# Wizard.net
KiCad netlist of a schematic drawn in EAGLE
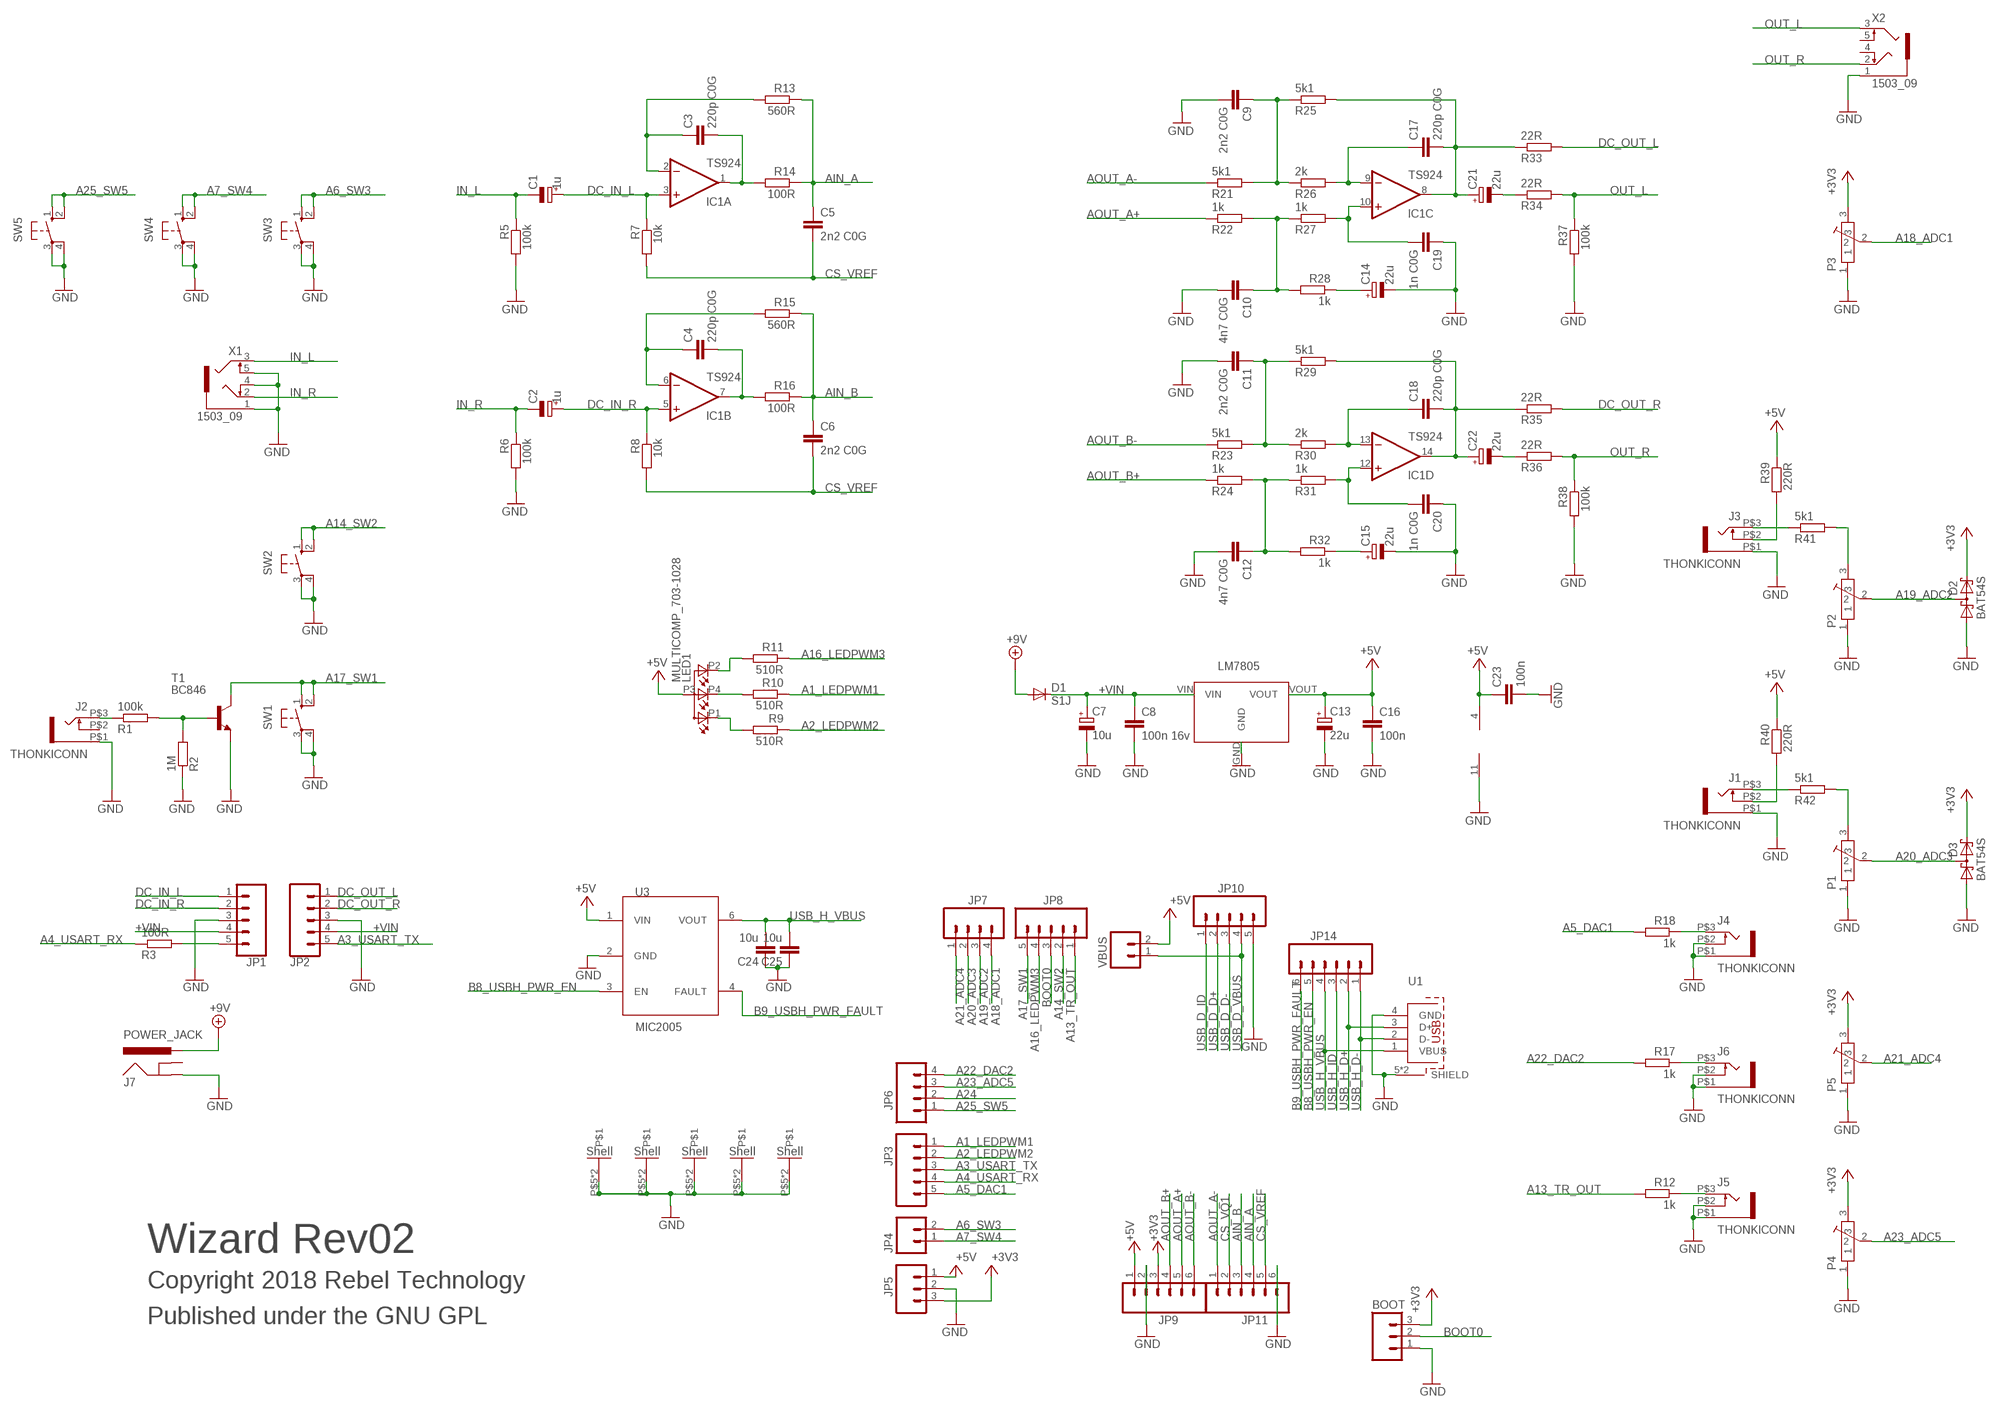
[diagram p0: schematic, sheet 1]

(export (version "E")
  (design (tool "Eeschema 10.0.6"))
  (components
    (comp (ref "BOOT")
      (value "M03PTH")
      (footprint "eagle-import:1X03")
      (libsource (lib "eagle-import") (part "M03PTH"))
    )
    (comp (ref "C1")
      (value "1u")
      (footprint "eagle-import:153CLV-0405")
      (libsource (lib "eagle-import") (part "CPOL-EU153CLV-0405"))
    )
    (comp (ref "C2")
      (value "1u")
      (footprint "eagle-import:153CLV-0405")
      (libsource (lib "eagle-import") (part "CPOL-EU153CLV-0405"))
    )
    (comp (ref "C3")
      (value "220p C0G")
      (footprint "eagle-import:C0603")
      (libsource (lib "eagle-import") (part "resistor_C-EUC0603"))
    )
    (comp (ref "C4")
      (value "220p C0G")
      (footprint "eagle-import:C0603")
      (libsource (lib "eagle-import") (part "resistor_C-EUC0603"))
    )
    (comp (ref "C5")
      (value "2n2 C0G")
      (footprint "eagle-import:C0603")
      (libsource (lib "eagle-import") (part "resistor_C-EUC0603"))
    )
    (comp (ref "C6")
      (value "2n2 C0G")
      (footprint "eagle-import:C0603")
      (libsource (lib "eagle-import") (part "resistor_C-EUC0603"))
    )
    (comp (ref "C7")
      (value "10u")
      (footprint "eagle-import:153CLV-0405")
      (libsource (lib "eagle-import") (part "CPOL-EU153CLV-0405"))
    )
    (comp (ref "C8")
      (value "100n 16v")
      (footprint "eagle-import:C0603")
      (libsource (lib "eagle-import") (part "C-EUC0603"))
    )
    (comp (ref "C9")
      (value "2n2 C0G")
      (footprint "eagle-import:C0603")
      (libsource (lib "eagle-import") (part "resistor_C-EUC0603"))
    )
    (comp (ref "C10")
      (value "4n7 C0G")
      (footprint "eagle-import:C0603")
      (libsource (lib "eagle-import") (part "resistor_C-EUC0603"))
    )
    (comp (ref "C11")
      (value "2n2 C0G")
      (footprint "eagle-import:C0603")
      (libsource (lib "eagle-import") (part "resistor_C-EUC0603"))
    )
    (comp (ref "C12")
      (value "4n7 C0G")
      (footprint "eagle-import:C0603")
      (libsource (lib "eagle-import") (part "resistor_C-EUC0603"))
    )
    (comp (ref "C13")
      (value "22u")
      (footprint "eagle-import:CPOL-5")
      (libsource (lib "eagle-import") (part "CPOL-EU153CLV-0505"))
    )
    (comp (ref "C14")
      (value "22u")
      (footprint "eagle-import:CPOL-5")
      (libsource (lib "eagle-import") (part "CPOL-EU153CLV-0505"))
    )
    (comp (ref "C15")
      (value "22u")
      (footprint "eagle-import:CPOL-5")
      (libsource (lib "eagle-import") (part "CPOL-EU153CLV-0505"))
    )
    (comp (ref "C16")
      (value "100n")
      (footprint "eagle-import:C0603")
      (libsource (lib "eagle-import") (part "C-EUC0603"))
    )
    (comp (ref "C17")
      (value "220p C0G")
      (footprint "eagle-import:C0603")
      (libsource (lib "eagle-import") (part "resistor_C-EUC0603"))
    )
    (comp (ref "C18")
      (value "220p C0G")
      (footprint "eagle-import:C0603")
      (libsource (lib "eagle-import") (part "resistor_C-EUC0603"))
    )
    (comp (ref "C19")
      (value "1n C0G")
      (footprint "eagle-import:C0603")
      (libsource (lib "eagle-import") (part "resistor_C-EUC0603"))
    )
    (comp (ref "C20")
      (value "1n C0G")
      (footprint "eagle-import:C0603")
      (libsource (lib "eagle-import") (part "resistor_C-EUC0603"))
    )
    (comp (ref "C21")
      (value "22u")
      (footprint "eagle-import:CPOL-5")
      (libsource (lib "eagle-import") (part "CPOL-EU153CLV-0505"))
    )
    (comp (ref "C22")
      (value "22u")
      (footprint "eagle-import:CPOL-5")
      (libsource (lib "eagle-import") (part "CPOL-EU153CLV-0505"))
    )
    (comp (ref "C23")
      (value "100n")
      (footprint "eagle-import:C0603")
      (libsource (lib "eagle-import") (part "resistor_C-EUC0603"))
    )
    (comp (ref "C24")
      (value "10u")
      (footprint "eagle-import:C0603")
      (libsource (lib "eagle-import") (part "resistor_C-EUC0603"))
    )
    (comp (ref "C25")
      (value "10u")
      (footprint "eagle-import:C0603")
      (libsource (lib "eagle-import") (part "resistor_C-EUC0603"))
    )
    (comp (ref "D1")
      (value "S1J")
      (footprint "eagle-import:SMA-DIODE")
      (libsource (lib "eagle-import") (part "DIODESMA"))
    )
    (comp (ref "D2")
      (value "BAT54S")
      (footprint "eagle-import:SOT23")
      (libsource (lib "eagle-import") (part "BAT54S"))
    )
    (comp (ref "D3")
      (value "BAT54S")
      (footprint "eagle-import:SOT23")
      (libsource (lib "eagle-import") (part "BAT54S"))
    )
    (comp (ref "IC1")
      (value "TS924")
      (footprint "eagle-import:SO14")
      (libsource (lib "eagle-import") (part "LM324D"))
    )
    (comp (ref "J1")
      (value "THONKICONN")
      (footprint "eagle-import:THONKICONN")
      (libsource (lib "eagle-import") (part "THONKICONN"))
    )
    (comp (ref "J2")
      (value "THONKICONN")
      (footprint "eagle-import:THONKICONN")
      (libsource (lib "eagle-import") (part "THONKICONN"))
    )
    (comp (ref "J3")
      (value "THONKICONN")
      (footprint "eagle-import:THONKICONN")
      (libsource (lib "eagle-import") (part "THONKICONN"))
    )
    (comp (ref "J4")
      (value "THONKICONN")
      (footprint "eagle-import:THONKICONN")
      (libsource (lib "eagle-import") (part "THONKICONN"))
    )
    (comp (ref "J5")
      (value "THONKICONN")
      (footprint "eagle-import:THONKICONN")
      (libsource (lib "eagle-import") (part "THONKICONN"))
    )
    (comp (ref "J6")
      (value "THONKICONN")
      (footprint "eagle-import:THONKICONN")
      (libsource (lib "eagle-import") (part "THONKICONN"))
    )
    (comp (ref "J7")
      (value "POWER_JACK")
      (footprint "eagle-import:DC_JACK_SLOT")
      (libsource (lib "eagle-import") (part "POWER_JACK"))
    )
    (comp (ref "JP1")
      (value "CONN_05JST-VERT")
      (footprint "eagle-import:JST-5-PTH-VERT")
      (libsource (lib "eagle-import") (part "CONN_05JST-VERT"))
    )
    (comp (ref "JP2")
      (value "CONN_05JST-VERT")
      (footprint "eagle-import:JST-5-PTH-VERT")
      (libsource (lib "eagle-import") (part "CONN_05JST-VERT"))
    )
    (comp (ref "JP3")
      (value "M05PTH")
      (footprint "eagle-import:1X05")
      (libsource (lib "eagle-import") (part "M05PTH"))
    )
    (comp (ref "JP4")
      (value "M02PTH")
      (footprint "eagle-import:1X02")
      (libsource (lib "eagle-import") (part "M02PTH"))
    )
    (comp (ref "JP5")
      (value "M03PTH")
      (footprint "eagle-import:1X03")
      (libsource (lib "eagle-import") (part "M03PTH"))
    )
    (comp (ref "JP6")
      (value "M04PTH")
      (footprint "eagle-import:1X04")
      (libsource (lib "eagle-import") (part "M04PTH"))
    )
    (comp (ref "JP7")
      (value "M04PTH")
      (footprint "eagle-import:1X04")
      (libsource (lib "eagle-import") (part "M04PTH"))
    )
    (comp (ref "JP8")
      (value "M05PTH")
      (footprint "eagle-import:1X05")
      (libsource (lib "eagle-import") (part "M05PTH"))
    )
    (comp (ref "JP9")
      (value "M06SIP")
      (footprint "eagle-import:1X06")
      (libsource (lib "eagle-import") (part "M06SIP"))
    )
    (comp (ref "JP10")
      (value "M05PTH")
      (footprint "eagle-import:1X05")
      (libsource (lib "eagle-import") (part "M05PTH"))
    )
    (comp (ref "JP11")
      (value "M06SIP")
      (footprint "eagle-import:1X06")
      (libsource (lib "eagle-import") (part "M06SIP"))
    )
    (comp (ref "JP14")
      (value "M06SIP")
      (footprint "eagle-import:1X06")
      (libsource (lib "eagle-import") (part "M06SIP"))
    )
    (comp (ref "LED1")
      (value "MULTICOMP_703-1028")
      (footprint "eagle-import:RGB-LED-703-1028")
      (libsource (lib "eagle-import") (part "MULTICOMP_703-1028"))
    )
    (comp (ref "P1")
      (value "POT-ALPS-RK09L1140")
      (footprint "eagle-import:POT-ALPS-RK09L1140")
      (libsource (lib "eagle-import") (part "POT-ALPS-RK09L1140"))
    )
    (comp (ref "P2")
      (value "POT-ALPS-RK09L1140")
      (footprint "eagle-import:POT-ALPS-RK09L1140")
      (libsource (lib "eagle-import") (part "POT-ALPS-RK09L1140"))
    )
    (comp (ref "P3")
      (value "POT-ALPS-RK09L1140")
      (footprint "eagle-import:POT-ALPS-RK09L1140")
      (libsource (lib "eagle-import") (part "POT-ALPS-RK09L1140"))
    )
    (comp (ref "P4")
      (value "POT-ALPS-RK09L1140")
      (footprint "eagle-import:POT-ALPS-RK09L1140")
      (libsource (lib "eagle-import") (part "POT-ALPS-RK09L1140"))
    )
    (comp (ref "P5")
      (value "POT-ALPS-RK09L1140")
      (footprint "eagle-import:POT-ALPS-RK09L1140")
      (libsource (lib "eagle-import") (part "POT-ALPS-RK09L1140"))
    )
    (comp (ref "R1")
      (value "100k")
      (footprint "eagle-import:0603")
      (libsource (lib "eagle-import") (part "R-EU_0603"))
    )
    (comp (ref "R2")
      (value "1M")
      (footprint "eagle-import:0603")
      (libsource (lib "eagle-import") (part "R-EU_0603"))
    )
    (comp (ref "R3")
      (value "100R")
      (footprint "eagle-import:0603")
      (libsource (lib "eagle-import") (part "R-EU_0603"))
    )
    (comp (ref "R5")
      (value "100k")
      (footprint "eagle-import:0603")
      (libsource (lib "eagle-import") (part "R-EU_0603"))
    )
    (comp (ref "R6")
      (value "100k")
      (footprint "eagle-import:0603")
      (libsource (lib "eagle-import") (part "R-EU_0603"))
    )
    (comp (ref "R7")
      (value "10k")
      (footprint "eagle-import:0603")
      (libsource (lib "eagle-import") (part "R-EU_0603"))
    )
    (comp (ref "R8")
      (value "10k")
      (footprint "eagle-import:0603")
      (libsource (lib "eagle-import") (part "R-EU_0603"))
    )
    (comp (ref "R9")
      (value "510R")
      (footprint "eagle-import:0603")
      (libsource (lib "eagle-import") (part "R-EU_0603"))
    )
    (comp (ref "R10")
      (value "510R")
      (footprint "eagle-import:0603")
      (libsource (lib "eagle-import") (part "R-EU_0603"))
    )
    (comp (ref "R11")
      (value "510R")
      (footprint "eagle-import:0603")
      (libsource (lib "eagle-import") (part "R-EU_0603"))
    )
    (comp (ref "R12")
      (value "1k")
      (footprint "eagle-import:0603")
      (libsource (lib "eagle-import") (part "R-EU_0603"))
    )
    (comp (ref "R13")
      (value "560R")
      (footprint "eagle-import:0603")
      (libsource (lib "eagle-import") (part "R-EU_0603"))
    )
    (comp (ref "R14")
      (value "100R")
      (footprint "eagle-import:0603")
      (libsource (lib "eagle-import") (part "R-EU_0603"))
    )
    (comp (ref "R15")
      (value "560R")
      (footprint "eagle-import:0603")
      (libsource (lib "eagle-import") (part "R-EU_0603"))
    )
    (comp (ref "R16")
      (value "100R")
      (footprint "eagle-import:0603")
      (libsource (lib "eagle-import") (part "R-EU_0603"))
    )
    (comp (ref "R17")
      (value "1k")
      (footprint "eagle-import:0603")
      (libsource (lib "eagle-import") (part "R-EU_0603"))
    )
    (comp (ref "R18")
      (value "1k")
      (footprint "eagle-import:0603")
      (libsource (lib "eagle-import") (part "R-EU_0603"))
    )
    (comp (ref "R21")
      (value "5k1")
      (footprint "eagle-import:0603")
      (libsource (lib "eagle-import") (part "R-EU_0603"))
    )
    (comp (ref "R22")
      (value "1k")
      (footprint "eagle-import:0603")
      (libsource (lib "eagle-import") (part "R-EU_0603"))
    )
    (comp (ref "R23")
      (value "5k1")
      (footprint "eagle-import:0603")
      (libsource (lib "eagle-import") (part "R-EU_0603"))
    )
    (comp (ref "R24")
      (value "1k")
      (footprint "eagle-import:0603")
      (libsource (lib "eagle-import") (part "R-EU_0603"))
    )
    (comp (ref "R25")
      (value "5k1")
      (footprint "eagle-import:0603")
      (libsource (lib "eagle-import") (part "R-EU_0603"))
    )
    (comp (ref "R26")
      (value "2k")
      (footprint "eagle-import:0603")
      (libsource (lib "eagle-import") (part "R-EU_0603"))
    )
    (comp (ref "R27")
      (value "1k")
      (footprint "eagle-import:0603")
      (libsource (lib "eagle-import") (part "R-EU_0603"))
    )
    (comp (ref "R28")
      (value "1k")
      (footprint "eagle-import:0603")
      (libsource (lib "eagle-import") (part "R-EU_0603"))
    )
    (comp (ref "R29")
      (value "5k1")
      (footprint "eagle-import:0603")
      (libsource (lib "eagle-import") (part "R-EU_0603"))
    )
    (comp (ref "R30")
      (value "2k")
      (footprint "eagle-import:0603")
      (libsource (lib "eagle-import") (part "R-EU_0603"))
    )
    (comp (ref "R31")
      (value "1k")
      (footprint "eagle-import:0603")
      (libsource (lib "eagle-import") (part "R-EU_0603"))
    )
    (comp (ref "R32")
      (value "1k")
      (footprint "eagle-import:0603")
      (libsource (lib "eagle-import") (part "R-EU_0603"))
    )
    (comp (ref "R33")
      (value "22R")
      (footprint "eagle-import:0603")
      (libsource (lib "eagle-import") (part "R-EU_0603"))
    )
    (comp (ref "R34")
      (value "22R")
      (footprint "eagle-import:0603")
      (libsource (lib "eagle-import") (part "R-EU_0603"))
    )
    (comp (ref "R35")
      (value "22R")
      (footprint "eagle-import:0603")
      (libsource (lib "eagle-import") (part "R-EU_0603"))
    )
    (comp (ref "R36")
      (value "22R")
      (footprint "eagle-import:0603")
      (libsource (lib "eagle-import") (part "R-EU_0603"))
    )
    (comp (ref "R37")
      (value "100k")
      (footprint "eagle-import:0603")
      (libsource (lib "eagle-import") (part "R-EU_0603"))
    )
    (comp (ref "R38")
      (value "100k")
      (footprint "eagle-import:0603")
      (libsource (lib "eagle-import") (part "R-EU_0603"))
    )
    (comp (ref "R39")
      (value "220R")
      (footprint "eagle-import:0603")
      (libsource (lib "eagle-import") (part "R-EU_0603"))
    )
    (comp (ref "R40")
      (value "220R")
      (footprint "eagle-import:0603")
      (libsource (lib "eagle-import") (part "R-EU_0603"))
    )
    (comp (ref "R41")
      (value "5k1")
      (footprint "eagle-import:0603")
      (libsource (lib "eagle-import") (part "R-EU_0603"))
    )
    (comp (ref "R42")
      (value "5k1")
      (footprint "eagle-import:0603")
      (libsource (lib "eagle-import") (part "R-EU_0603"))
    )
    (comp (ref "SW1")
      (value "10-XX")
      (footprint "eagle-import:B3F-10XX")
      (fields (field (name "MPN") "B3F-1000"))
      (libsource (lib "eagle-import") (part "10-XX"))
    )
    (comp (ref "SW2")
      (value "10-XX")
      (footprint "eagle-import:B3F-10XX")
      (fields (field (name "MPN") "B3F-1000"))
      (libsource (lib "eagle-import") (part "10-XX"))
    )
    (comp (ref "SW3")
      (value "10-XX")
      (footprint "eagle-import:B3F-10XX")
      (fields (field (name "MPN") "B3F-1000"))
      (libsource (lib "eagle-import") (part "10-XX"))
    )
    (comp (ref "SW4")
      (value "10-XX")
      (footprint "eagle-import:B3F-10XX")
      (fields (field (name "MPN") "B3F-1000"))
      (libsource (lib "eagle-import") (part "10-XX"))
    )
    (comp (ref "SW5")
      (value "10-XX")
      (footprint "eagle-import:B3F-10XX")
      (fields (field (name "MPN") "B3F-1000"))
      (libsource (lib "eagle-import") (part "10-XX"))
    )
    (comp (ref "T1")
      (value "BC846")
      (footprint "eagle-import:SOT23")
      (libsource (lib "eagle-import") (part "BC846"))
    )
    (comp (ref "U1")
      (value "614104190121")
      (footprint "eagle-import:614104190121")
      (libsource (lib "eagle-import") (part "614104190121"))
    )
    (comp (ref "U2")
      (value "LM7805")
      (footprint "eagle-import:REG_S9V11F5")
      (libsource (lib "eagle-import") (part "REG_S9V11F5"))
    )
    (comp (ref "U3")
      (value "MIC2005")
      (footprint "eagle-import:SOT23-6")
      (libsource (lib "eagle-import") (part "MIC2005"))
    )
    (comp (ref "VBUS")
      (value "M02PTH")
      (footprint "eagle-import:1X02")
      (libsource (lib "eagle-import") (part "M02PTH"))
    )
    (comp (ref "X1")
      (value "1503_09")
      (footprint "eagle-import:1503_09")
      (libsource (lib "eagle-import") (part "1503_09"))
    )
    (comp (ref "X2")
      (value "1503_09")
      (footprint "eagle-import:1503_09")
      (libsource (lib "eagle-import") (part "1503_09"))
    )
  )
  (nets
    (net (code "1") (name "+3V3") (class "Default")
      (node (ref "BOOT") (pin "3") (pinfunction "3_3") (pintype "passive"))
      (node (ref "D2") (pin "2") (pinfunction "C2_2") (pintype "passive"))
      (node (ref "D3") (pin "2") (pinfunction "C2_2") (pintype "passive"))
      (node (ref "JP5") (pin "3") (pinfunction "3_3") (pintype "passive"))
      (node (ref "JP9") (pin "3") (pinfunction "3_3") (pintype "passive"))
      (node (ref "P3") (pin "3") (pinfunction "3_3") (pintype "bidirectional"))
      (node (ref "P4") (pin "3") (pinfunction "3_3") (pintype "bidirectional"))
      (node (ref "P5") (pin "3") (pinfunction "3_3") (pintype "bidirectional"))
    )
    (net (code "2") (name "+5V") (class "Default")
      (node (ref "C13") (pin "+") (pinfunction "+_+") (pintype "passive"))
      (node (ref "C16") (pin "1") (pinfunction "1_1") (pintype "passive"))
      (node (ref "C23") (pin "1") (pinfunction "1_1") (pintype "passive"))
      (node (ref "IC1") (pin "4") (pinfunction "V+_4") (pintype "power_in"))
      (node (ref "JP5") (pin "1") (pinfunction "1_1") (pintype "passive"))
      (node (ref "JP9") (pin "1") (pinfunction "1_1") (pintype "passive"))
      (node (ref "LED1") (pin "P3") (pinfunction "A_P3") (pintype "passive"))
      (node (ref "R39") (pin "1") (pinfunction "1_1") (pintype "passive"))
      (node (ref "R40") (pin "1") (pinfunction "1_1") (pintype "passive"))
      (node (ref "U2") (pin "VOUT") (pinfunction "VOUT_VOUT") (pintype "output"))
      (node (ref "U3") (pin "1") (pinfunction "VIN_1") (pintype "power_in"))
      (node (ref "VBUS") (pin "2") (pinfunction "2_2") (pintype "passive"))
    )
    (net (code "3") (name "+9V") (class "Default")
      (node (ref "D1") (pin "A") (pinfunction "A_A") (pintype "passive"))
      (node (ref "J7") (pin "PWR") (pinfunction "PWR_PWR") (pintype "bidirectional"))
    )
    (net (code "4") (name "/+VIN") (class "Default")
      (node (ref "C7") (pin "+") (pinfunction "+_+") (pintype "passive"))
      (node (ref "C8") (pin "1") (pinfunction "1_1") (pintype "passive"))
      (node (ref "D1") (pin "C") (pinfunction "C_C") (pintype "passive"))
      (node (ref "JP1") (pin "4") (pinfunction "4_4") (pintype "passive"))
      (node (ref "JP2") (pin "4") (pinfunction "4_4") (pintype "passive"))
      (node (ref "U2") (pin "VIN") (pinfunction "VIN_VIN") (pintype "input"))
    )
    (net (code "5") (name "/A1_LEDPWM1") (class "Default")
      (node (ref "JP3") (pin "1") (pinfunction "1_1") (pintype "passive"))
      (node (ref "R10") (pin "1") (pinfunction "1_1") (pintype "passive"))
    )
    (net (code "6") (name "/A2_LEDPWM2") (class "Default")
      (node (ref "JP3") (pin "2") (pinfunction "2_2") (pintype "passive"))
      (node (ref "R9") (pin "1") (pinfunction "1_1") (pintype "passive"))
    )
    (net (code "7") (name "/A3_USART_TX") (class "Default")
      (node (ref "JP2") (pin "5") (pinfunction "5_5") (pintype "passive"))
      (node (ref "JP3") (pin "3") (pinfunction "3_3") (pintype "passive"))
    )
    (net (code "8") (name "/A4_USART_RX") (class "Default")
      (node (ref "JP3") (pin "4") (pinfunction "4_4") (pintype "passive"))
      (node (ref "R3") (pin "1") (pinfunction "1_1") (pintype "passive"))
    )
    (net (code "9") (name "/A5_DAC1") (class "Default")
      (node (ref "JP3") (pin "5") (pinfunction "5_5") (pintype "passive"))
      (node (ref "R18") (pin "2") (pinfunction "2_2") (pintype "passive"))
    )
    (net (code "10") (name "/A6_SW3") (class "Default")
      (node (ref "JP4") (pin "2") (pinfunction "2_2") (pintype "passive"))
      (node (ref "SW3") (pin "1") (pinfunction "S_1") (pintype "passive"))
      (node (ref "SW3") (pin "2") (pinfunction "S1_2") (pintype "passive"))
    )
    (net (code "11") (name "/A7_SW4") (class "Default")
      (node (ref "JP4") (pin "1") (pinfunction "1_1") (pintype "passive"))
      (node (ref "SW4") (pin "1") (pinfunction "S_1") (pintype "passive"))
      (node (ref "SW4") (pin "2") (pinfunction "S1_2") (pintype "passive"))
    )
    (net (code "12") (name "/A13_TR_OUT") (class "Default")
      (node (ref "JP8") (pin "1") (pinfunction "1_1") (pintype "passive"))
      (node (ref "R12") (pin "2") (pinfunction "2_2") (pintype "passive"))
    )
    (net (code "13") (name "/A14_SW2") (class "Default")
      (node (ref "JP8") (pin "2") (pinfunction "2_2") (pintype "passive"))
      (node (ref "SW2") (pin "1") (pinfunction "S_1") (pintype "passive"))
      (node (ref "SW2") (pin "2") (pinfunction "S1_2") (pintype "passive"))
    )
    (net (code "14") (name "/A16_LEDPWM3") (class "Default")
      (node (ref "JP8") (pin "4") (pinfunction "4_4") (pintype "passive"))
      (node (ref "R11") (pin "1") (pinfunction "1_1") (pintype "passive"))
    )
    (net (code "15") (name "/A17_SW1") (class "Default")
      (node (ref "JP8") (pin "5") (pinfunction "5_5") (pintype "passive"))
      (node (ref "SW1") (pin "1") (pinfunction "S_1") (pintype "passive"))
      (node (ref "SW1") (pin "2") (pinfunction "S1_2") (pintype "passive"))
      (node (ref "T1") (pin "3") (pinfunction "C_3") (pintype "passive"))
    )
    (net (code "16") (name "/A18_ADC1") (class "Default")
      (node (ref "JP7") (pin "4") (pinfunction "4_4") (pintype "passive"))
      (node (ref "P3") (pin "2") (pinfunction "2_2") (pintype "bidirectional"))
    )
    (net (code "17") (name "/A19_ADC2") (class "Default")
      (node (ref "D2") (pin "3") (pinfunction "C1A2_3") (pintype "passive"))
      (node (ref "JP7") (pin "3") (pinfunction "3_3") (pintype "passive"))
      (node (ref "P2") (pin "2") (pinfunction "2_2") (pintype "bidirectional"))
    )
    (net (code "18") (name "/A20_ADC3") (class "Default")
      (node (ref "D3") (pin "3") (pinfunction "C1A2_3") (pintype "passive"))
      (node (ref "JP7") (pin "2") (pinfunction "2_2") (pintype "passive"))
      (node (ref "P1") (pin "2") (pinfunction "2_2") (pintype "bidirectional"))
    )
    (net (code "19") (name "/A21_ADC4") (class "Default")
      (node (ref "JP7") (pin "1") (pinfunction "1_1") (pintype "passive"))
      (node (ref "P5") (pin "2") (pinfunction "2_2") (pintype "bidirectional"))
    )
    (net (code "20") (name "/A22_DAC2") (class "Default")
      (node (ref "JP6") (pin "4") (pinfunction "4_4") (pintype "passive"))
      (node (ref "R17") (pin "2") (pinfunction "2_2") (pintype "passive"))
    )
    (net (code "21") (name "/A23_ADC5") (class "Default")
      (node (ref "JP6") (pin "3") (pinfunction "3_3") (pintype "passive"))
      (node (ref "P4") (pin "2") (pinfunction "2_2") (pintype "bidirectional"))
    )
    (net (code "22") (name "/A24") (class "Default")
      (node (ref "JP6") (pin "2") (pinfunction "2_2") (pintype "passive"))
    )
    (net (code "23") (name "/A25_SW5") (class "Default")
      (node (ref "JP6") (pin "1") (pinfunction "1_1") (pintype "passive"))
      (node (ref "SW5") (pin "1") (pinfunction "S_1") (pintype "passive"))
      (node (ref "SW5") (pin "2") (pinfunction "S1_2") (pintype "passive"))
    )
    (net (code "24") (name "/AIN_A") (class "Default")
      (node (ref "C5") (pin "1") (pinfunction "1_1") (pintype "passive"))
      (node (ref "JP11") (pin "4") (pinfunction "4_4") (pintype "passive"))
      (node (ref "R13") (pin "1") (pinfunction "1_1") (pintype "passive"))
      (node (ref "R14") (pin "1") (pinfunction "1_1") (pintype "passive"))
    )
    (net (code "25") (name "/AIN_B") (class "Default")
      (node (ref "C6") (pin "1") (pinfunction "1_1") (pintype "passive"))
      (node (ref "JP11") (pin "3") (pinfunction "3_3") (pintype "passive"))
      (node (ref "R15") (pin "1") (pinfunction "1_1") (pintype "passive"))
      (node (ref "R16") (pin "1") (pinfunction "1_1") (pintype "passive"))
    )
    (net (code "26") (name "/AOUT_A+") (class "Default")
      (node (ref "JP9") (pin "5") (pinfunction "5_5") (pintype "passive"))
      (node (ref "R22") (pin "1") (pinfunction "1_1") (pintype "passive"))
    )
    (net (code "27") (name "/AOUT_A-") (class "Default")
      (node (ref "JP11") (pin "1") (pinfunction "1_1") (pintype "passive"))
      (node (ref "R21") (pin "1") (pinfunction "1_1") (pintype "passive"))
    )
    (net (code "28") (name "/AOUT_B+") (class "Default")
      (node (ref "JP9") (pin "4") (pinfunction "4_4") (pintype "passive"))
      (node (ref "R24") (pin "1") (pinfunction "1_1") (pintype "passive"))
    )
    (net (code "29") (name "/AOUT_B-") (class "Default")
      (node (ref "JP9") (pin "6") (pinfunction "6_6") (pintype "passive"))
      (node (ref "R23") (pin "1") (pinfunction "1_1") (pintype "passive"))
    )
    (net (code "30") (name "/B8_USBH_PWR_EN") (class "Default")
      (node (ref "JP14") (pin "5") (pinfunction "5_5") (pintype "passive"))
      (node (ref "U3") (pin "3") (pinfunction "EN_3") (pintype "input"))
    )
    (net (code "31") (name "/B9_USBH_PWR_FAULT") (class "Default")
      (node (ref "JP14") (pin "6") (pinfunction "6_6") (pintype "passive"))
      (node (ref "U3") (pin "4") (pinfunction "FAULT_4") (pintype "output"))
    )
    (net (code "32") (name "/BOOT0") (class "Default")
      (node (ref "BOOT") (pin "2") (pinfunction "2_2") (pintype "passive"))
      (node (ref "JP8") (pin "3") (pinfunction "3_3") (pintype "passive"))
    )
    (net (code "33") (name "/CS_VQ1") (class "Default")
      (node (ref "JP11") (pin "2") (pinfunction "2_2") (pintype "passive"))
    )
    (net (code "34") (name "/CS_VREF") (class "Default")
      (node (ref "C5") (pin "2") (pinfunction "2_2") (pintype "passive"))
      (node (ref "C6") (pin "2") (pinfunction "2_2") (pintype "passive"))
      (node (ref "JP11") (pin "5") (pinfunction "5_5") (pintype "passive"))
      (node (ref "R7") (pin "2") (pinfunction "2_2") (pintype "passive"))
      (node (ref "R8") (pin "2") (pinfunction "2_2") (pintype "passive"))
    )
    (net (code "35") (name "/DC_IN_L") (class "Default")
      (node (ref "C1") (pin "+") (pinfunction "+_+") (pintype "passive"))
      (node (ref "IC1") (pin "3") (pinfunction "+IN_3") (pintype "input"))
      (node (ref "JP1") (pin "1") (pinfunction "1_1") (pintype "passive"))
      (node (ref "R7") (pin "1") (pinfunction "1_1") (pintype "passive"))
    )
    (net (code "36") (name "/DC_IN_R") (class "Default")
      (node (ref "C2") (pin "+") (pinfunction "+_+") (pintype "passive"))
      (node (ref "IC1") (pin "5") (pinfunction "+IN_5") (pintype "input"))
      (node (ref "JP1") (pin "2") (pinfunction "2_2") (pintype "passive"))
      (node (ref "R8") (pin "1") (pinfunction "1_1") (pintype "passive"))
    )
    (net (code "37") (name "/DC_OUT_L") (class "Default")
      (node (ref "JP2") (pin "1") (pinfunction "1_1") (pintype "passive"))
      (node (ref "R33") (pin "2") (pinfunction "2_2") (pintype "passive"))
    )
    (net (code "38") (name "/DC_OUT_R") (class "Default")
      (node (ref "JP2") (pin "2") (pinfunction "2_2") (pintype "passive"))
      (node (ref "R35") (pin "2") (pinfunction "2_2") (pintype "passive"))
    )
    (net (code "39") (name "/IN_L") (class "Default")
      (node (ref "C1") (pin "-") (pinfunction "-_-") (pintype "passive"))
      (node (ref "R5") (pin "1") (pinfunction "1_1") (pintype "passive"))
      (node (ref "X1") (pin "3") (pinfunction "3_3") (pintype "passive"))
    )
    (net (code "40") (name "/IN_R") (class "Default")
      (node (ref "C2") (pin "-") (pinfunction "-_-") (pintype "passive"))
      (node (ref "R6") (pin "1") (pinfunction "1_1") (pintype "passive"))
      (node (ref "X1") (pin "2") (pinfunction "2_2") (pintype "passive"))
    )
    (net (code "41") (name "/OUT_L") (class "Default")
      (node (ref "R34") (pin "2") (pinfunction "2_2") (pintype "passive"))
      (node (ref "R37") (pin "1") (pinfunction "1_1") (pintype "passive"))
      (node (ref "X2") (pin "3") (pinfunction "3_3") (pintype "passive"))
    )
    (net (code "42") (name "/OUT_R") (class "Default")
      (node (ref "R36") (pin "2") (pinfunction "2_2") (pintype "passive"))
      (node (ref "R38") (pin "1") (pinfunction "1_1") (pintype "passive"))
      (node (ref "X2") (pin "2") (pinfunction "2_2") (pintype "passive"))
    )
    (net (code "43") (name "/USB_D_D+") (class "Default")
      (node (ref "JP10") (pin "2") (pinfunction "2_2") (pintype "passive"))
    )
    (net (code "44") (name "/USB_D_D-") (class "Default")
      (node (ref "JP10") (pin "3") (pinfunction "3_3") (pintype "passive"))
    )
    (net (code "45") (name "/USB_D_ID") (class "Default")
      (node (ref "JP10") (pin "1") (pinfunction "1_1") (pintype "passive"))
    )
    (net (code "46") (name "/USB_D_VBUS") (class "Default")
      (node (ref "JP10") (pin "4") (pinfunction "4_4") (pintype "passive"))
      (node (ref "VBUS") (pin "1") (pinfunction "1_1") (pintype "passive"))
    )
    (net (code "47") (name "/USB_H_D+") (class "Default")
      (node (ref "JP14") (pin "2") (pinfunction "2_2") (pintype "passive"))
      (node (ref "U1") (pin "3") (pinfunction "D+_3") (pintype "bidirectional"))
    )
    (net (code "48") (name "/USB_H_D-") (class "Default")
      (node (ref "JP14") (pin "1") (pinfunction "1_1") (pintype "passive"))
      (node (ref "U1") (pin "2") (pinfunction "D-_2") (pintype "bidirectional"))
    )
    (net (code "49") (name "/USB_H_ID") (class "Default")
      (node (ref "JP14") (pin "3") (pinfunction "3_3") (pintype "passive"))
    )
    (net (code "50") (name "/USB_H_VBUS") (class "Default")
      (node (ref "C24") (pin "2") (pinfunction "2_2") (pintype "passive"))
      (node (ref "C25") (pin "2") (pinfunction "2_2") (pintype "passive"))
      (node (ref "JP14") (pin "4") (pinfunction "4_4") (pintype "passive"))
      (node (ref "U1") (pin "1") (pinfunction "VBUS_1") (pintype "bidirectional"))
      (node (ref "U3") (pin "6") (pinfunction "VOUT_6") (pintype "output"))
    )
    (net (code "51") (name "GND") (class "Default")
      (node (ref "BOOT") (pin "1") (pinfunction "1_1") (pintype "passive"))
      (node (ref "C10") (pin "2") (pinfunction "2_2") (pintype "passive"))
      (node (ref "C11") (pin "2") (pinfunction "2_2") (pintype "passive"))
      (node (ref "C12") (pin "2") (pinfunction "2_2") (pintype "passive"))
      (node (ref "C13") (pin "-") (pinfunction "-_-") (pintype "passive"))
      (node (ref "C14") (pin "-") (pinfunction "-_-") (pintype "passive"))
      (node (ref "C15") (pin "-") (pinfunction "-_-") (pintype "passive"))
      (node (ref "C16") (pin "2") (pinfunction "2_2") (pintype "passive"))
      (node (ref "C19") (pin "1") (pinfunction "1_1") (pintype "passive"))
      (node (ref "C20") (pin "1") (pinfunction "1_1") (pintype "passive"))
      (node (ref "C23") (pin "2") (pinfunction "2_2") (pintype "passive"))
      (node (ref "C24") (pin "1") (pinfunction "1_1") (pintype "passive"))
      (node (ref "C25") (pin "1") (pinfunction "1_1") (pintype "passive"))
      (node (ref "C7") (pin "-") (pinfunction "-_-") (pintype "passive"))
      (node (ref "C8") (pin "2") (pinfunction "2_2") (pintype "passive"))
      (node (ref "C9") (pin "2") (pinfunction "2_2") (pintype "passive"))
      (node (ref "D2") (pin "1") (pinfunction "A1_1") (pintype "passive"))
      (node (ref "D3") (pin "1") (pinfunction "A1_1") (pintype "passive"))
      (node (ref "IC1") (pin "11") (pinfunction "V-_11") (pintype "power_in"))
      (node (ref "J1") (pin "P$1") (pinfunction "5_P$1") (pintype "passive"))
      (node (ref "J2") (pin "P$1") (pinfunction "5_P$1") (pintype "passive"))
      (node (ref "J3") (pin "P$1") (pinfunction "5_P$1") (pintype "passive"))
      (node (ref "J4") (pin "P$1") (pinfunction "5_P$1") (pintype "passive"))
      (node (ref "J4") (pin "P$2") (pinfunction "4_P$2") (pintype "passive"))
      (node (ref "J5") (pin "P$1") (pinfunction "5_P$1") (pintype "passive"))
      (node (ref "J5") (pin "P$2") (pinfunction "4_P$2") (pintype "passive"))
      (node (ref "J6") (pin "P$1") (pinfunction "5_P$1") (pintype "passive"))
      (node (ref "J6") (pin "P$2") (pinfunction "4_P$2") (pintype "passive"))
      (node (ref "J7") (pin "GND") (pinfunction "GND_GND") (pintype "bidirectional"))
      (node (ref "JP1") (pin "3") (pinfunction "3_3") (pintype "passive"))
      (node (ref "JP10") (pin "5") (pinfunction "5_5") (pintype "passive"))
      (node (ref "JP11") (pin "6") (pinfunction "6_6") (pintype "passive"))
      (node (ref "JP2") (pin "3") (pinfunction "3_3") (pintype "passive"))
      (node (ref "JP5") (pin "2") (pinfunction "2_2") (pintype "passive"))
      (node (ref "JP9") (pin "2") (pinfunction "2_2") (pintype "passive"))
      (node (ref "P1") (pin "1") (pinfunction "1_1") (pintype "bidirectional"))
      (node (ref "P1") (pin "P$5") (pinfunction "P$1_P$5") (pintype "bidirectional"))
      (node (ref "P1") (pin "P$6") (pinfunction "P$1_P$6") (pintype "bidirectional"))
      (node (ref "P2") (pin "1") (pinfunction "1_1") (pintype "bidirectional"))
      (node (ref "P2") (pin "P$5") (pinfunction "P$1_P$5") (pintype "bidirectional"))
      (node (ref "P2") (pin "P$6") (pinfunction "P$1_P$6") (pintype "bidirectional"))
      (node (ref "P3") (pin "1") (pinfunction "1_1") (pintype "bidirectional"))
      (node (ref "P3") (pin "P$5") (pinfunction "P$1_P$5") (pintype "bidirectional"))
      (node (ref "P3") (pin "P$6") (pinfunction "P$1_P$6") (pintype "bidirectional"))
      (node (ref "P4") (pin "1") (pinfunction "1_1") (pintype "bidirectional"))
      (node (ref "P4") (pin "P$5") (pinfunction "P$1_P$5") (pintype "bidirectional"))
      (node (ref "P4") (pin "P$6") (pinfunction "P$1_P$6") (pintype "bidirectional"))
      (node (ref "P5") (pin "1") (pinfunction "1_1") (pintype "bidirectional"))
      (node (ref "P5") (pin "P$5") (pinfunction "P$1_P$5") (pintype "bidirectional"))
      (node (ref "P5") (pin "P$6") (pinfunction "P$1_P$6") (pintype "bidirectional"))
      (node (ref "R2") (pin "1") (pinfunction "1_1") (pintype "passive"))
      (node (ref "R37") (pin "2") (pinfunction "2_2") (pintype "passive"))
      (node (ref "R38") (pin "2") (pinfunction "2_2") (pintype "passive"))
      (node (ref "R5") (pin "2") (pinfunction "2_2") (pintype "passive"))
      (node (ref "R6") (pin "2") (pinfunction "2_2") (pintype "passive"))
      (node (ref "SW1") (pin "3") (pinfunction "P_3") (pintype "passive"))
      (node (ref "SW1") (pin "4") (pinfunction "P1_4") (pintype "passive"))
      (node (ref "SW2") (pin "3") (pinfunction "P_3") (pintype "passive"))
      (node (ref "SW2") (pin "4") (pinfunction "P1_4") (pintype "passive"))
      (node (ref "SW3") (pin "3") (pinfunction "P_3") (pintype "passive"))
      (node (ref "SW3") (pin "4") (pinfunction "P1_4") (pintype "passive"))
      (node (ref "SW4") (pin "3") (pinfunction "P_3") (pintype "passive"))
      (node (ref "SW4") (pin "4") (pinfunction "P1_4") (pintype "passive"))
      (node (ref "SW5") (pin "3") (pinfunction "P_3") (pintype "passive"))
      (node (ref "SW5") (pin "4") (pinfunction "P1_4") (pintype "passive"))
      (node (ref "T1") (pin "2") (pinfunction "E_2") (pintype "passive"))
      (node (ref "U1") (pin "4") (pinfunction "GND_4") (pintype "bidirectional"))
      (node (ref "U1") (pin "5") (pinfunction "SHIELD_5") (pintype "bidirectional"))
      (node (ref "U1") (pin "6") (pinfunction "SHIELD_6") (pintype "bidirectional"))
      (node (ref "U2") (pin "GND") (pinfunction "GND_GND") (pintype "power_in"))
      (node (ref "U3") (pin "2") (pinfunction "GND_2") (pintype "power_in"))
      (node (ref "X1") (pin "1") (pinfunction "1_1") (pintype "passive"))
      (node (ref "X1") (pin "4") (pinfunction "4_4") (pintype "passive"))
      (node (ref "X1") (pin "5") (pinfunction "5_5") (pintype "passive"))
      (node (ref "X2") (pin "1") (pinfunction "1_1") (pintype "passive"))
    )
    (net (code "52") (name "Net-(C9-Pad1)") (class "Default")
      (node (ref "C9") (pin "1") (pinfunction "1_1") (pintype "passive"))
      (node (ref "R21") (pin "2") (pinfunction "2_2") (pintype "passive"))
      (node (ref "R25") (pin "1") (pinfunction "1_1") (pintype "passive"))
      (node (ref "R26") (pin "1") (pinfunction "1_1") (pintype "passive"))
    )
    (net (code "53") (name "Net-(C10-Pad1)") (class "Default")
      (node (ref "C10") (pin "1") (pinfunction "1_1") (pintype "passive"))
      (node (ref "R22") (pin "2") (pinfunction "2_2") (pintype "passive"))
      (node (ref "R27") (pin "1") (pinfunction "1_1") (pintype "passive"))
      (node (ref "R28") (pin "2") (pinfunction "2_2") (pintype "passive"))
    )
    (net (code "54") (name "Net-(C11-Pad1)") (class "Default")
      (node (ref "C11") (pin "1") (pinfunction "1_1") (pintype "passive"))
      (node (ref "R23") (pin "2") (pinfunction "2_2") (pintype "passive"))
      (node (ref "R29") (pin "1") (pinfunction "1_1") (pintype "passive"))
      (node (ref "R30") (pin "1") (pinfunction "1_1") (pintype "passive"))
    )
    (net (code "55") (name "Net-(C12-Pad1)") (class "Default")
      (node (ref "C12") (pin "1") (pinfunction "1_1") (pintype "passive"))
      (node (ref "R24") (pin "2") (pinfunction "2_2") (pintype "passive"))
      (node (ref "R31") (pin "1") (pinfunction "1_1") (pintype "passive"))
      (node (ref "R32") (pin "2") (pinfunction "2_2") (pintype "passive"))
    )
    (net (code "56") (name "Net-(C14-Pad+)") (class "Default")
      (node (ref "C14") (pin "+") (pinfunction "+_+") (pintype "passive"))
      (node (ref "R28") (pin "1") (pinfunction "1_1") (pintype "passive"))
    )
    (net (code "57") (name "Net-(C15-Pad+)") (class "Default")
      (node (ref "C15") (pin "+") (pinfunction "+_+") (pintype "passive"))
      (node (ref "R32") (pin "1") (pinfunction "1_1") (pintype "passive"))
    )
    (net (code "58") (name "Net-(C21-Pad-)") (class "Default")
      (node (ref "C21") (pin "-") (pinfunction "-_-") (pintype "passive"))
      (node (ref "R34") (pin "1") (pinfunction "1_1") (pintype "passive"))
    )
    (net (code "59") (name "Net-(C22-Pad-)") (class "Default")
      (node (ref "C22") (pin "-") (pinfunction "-_-") (pintype "passive"))
      (node (ref "R36") (pin "1") (pinfunction "1_1") (pintype "passive"))
    )
    (net (code "60") (name "Net-(IC1A--IN)") (class "Default")
      (node (ref "C3") (pin "1") (pinfunction "1_1") (pintype "passive"))
      (node (ref "IC1") (pin "2") (pinfunction "-IN_2") (pintype "input"))
      (node (ref "R13") (pin "2") (pinfunction "2_2") (pintype "passive"))
    )
    (net (code "61") (name "Net-(IC1A-OUT)") (class "Default")
      (node (ref "C3") (pin "2") (pinfunction "2_2") (pintype "passive"))
      (node (ref "IC1") (pin "1") (pinfunction "OUT_1") (pintype "output"))
      (node (ref "R14") (pin "2") (pinfunction "2_2") (pintype "passive"))
    )
    (net (code "62") (name "Net-(IC1B--IN)") (class "Default")
      (node (ref "C4") (pin "1") (pinfunction "1_1") (pintype "passive"))
      (node (ref "IC1") (pin "6") (pinfunction "-IN_6") (pintype "input"))
      (node (ref "R15") (pin "2") (pinfunction "2_2") (pintype "passive"))
    )
    (net (code "63") (name "Net-(IC1B-OUT)") (class "Default")
      (node (ref "C4") (pin "2") (pinfunction "2_2") (pintype "passive"))
      (node (ref "IC1") (pin "7") (pinfunction "OUT_7") (pintype "output"))
      (node (ref "R16") (pin "2") (pinfunction "2_2") (pintype "passive"))
    )
    (net (code "64") (name "Net-(IC1C-+IN)") (class "Default")
      (node (ref "C19") (pin "2") (pinfunction "2_2") (pintype "passive"))
      (node (ref "IC1") (pin "10") (pinfunction "+IN_10") (pintype "input"))
      (node (ref "R27") (pin "2") (pinfunction "2_2") (pintype "passive"))
    )
    (net (code "65") (name "Net-(IC1C--IN)") (class "Default")
      (node (ref "C17") (pin "1") (pinfunction "1_1") (pintype "passive"))
      (node (ref "IC1") (pin "9") (pinfunction "-IN_9") (pintype "input"))
      (node (ref "R26") (pin "2") (pinfunction "2_2") (pintype "passive"))
    )
    (net (code "66") (name "Net-(IC1C-OUT)") (class "Default")
      (node (ref "C17") (pin "2") (pinfunction "2_2") (pintype "passive"))
      (node (ref "C21") (pin "+") (pinfunction "+_+") (pintype "passive"))
      (node (ref "IC1") (pin "8") (pinfunction "OUT_8") (pintype "output"))
      (node (ref "R25") (pin "2") (pinfunction "2_2") (pintype "passive"))
      (node (ref "R33") (pin "1") (pinfunction "1_1") (pintype "passive"))
    )
    (net (code "67") (name "Net-(IC1D-+IN)") (class "Default")
      (node (ref "C20") (pin "2") (pinfunction "2_2") (pintype "passive"))
      (node (ref "IC1") (pin "12") (pinfunction "+IN_12") (pintype "input"))
      (node (ref "R31") (pin "2") (pinfunction "2_2") (pintype "passive"))
    )
    (net (code "68") (name "Net-(IC1D--IN)") (class "Default")
      (node (ref "C18") (pin "1") (pinfunction "1_1") (pintype "passive"))
      (node (ref "IC1") (pin "13") (pinfunction "-IN_13") (pintype "input"))
      (node (ref "R30") (pin "2") (pinfunction "2_2") (pintype "passive"))
    )
    (net (code "69") (name "Net-(IC1D-OUT)") (class "Default")
      (node (ref "C18") (pin "2") (pinfunction "2_2") (pintype "passive"))
      (node (ref "C22") (pin "+") (pinfunction "+_+") (pintype "passive"))
      (node (ref "IC1") (pin "14") (pinfunction "OUT_14") (pintype "output"))
      (node (ref "R29") (pin "2") (pinfunction "2_2") (pintype "passive"))
      (node (ref "R35") (pin "1") (pinfunction "1_1") (pintype "passive"))
    )
    (net (code "70") (name "Net-(J1-3)") (class "Default")
      (node (ref "J1") (pin "P$3") (pinfunction "3_P$3") (pintype "passive"))
      (node (ref "R42") (pin "1") (pinfunction "1_1") (pintype "passive"))
    )
    (net (code "71") (name "Net-(J1-4)") (class "Default")
      (node (ref "J1") (pin "P$2") (pinfunction "4_P$2") (pintype "passive"))
      (node (ref "R40") (pin "2") (pinfunction "2_2") (pintype "passive"))
    )
    (net (code "72") (name "Net-(J2-3)") (class "Default")
      (node (ref "J2") (pin "P$3") (pinfunction "3_P$3") (pintype "passive"))
      (node (ref "R1") (pin "1") (pinfunction "1_1") (pintype "passive"))
    )
    (net (code "73") (name "Net-(J3-3)") (class "Default")
      (node (ref "J3") (pin "P$3") (pinfunction "3_P$3") (pintype "passive"))
      (node (ref "R41") (pin "1") (pinfunction "1_1") (pintype "passive"))
    )
    (net (code "74") (name "Net-(J3-4)") (class "Default")
      (node (ref "J3") (pin "P$2") (pinfunction "4_P$2") (pintype "passive"))
      (node (ref "R39") (pin "2") (pinfunction "2_2") (pintype "passive"))
    )
    (net (code "75") (name "Net-(J4-3)") (class "Default")
      (node (ref "J4") (pin "P$3") (pinfunction "3_P$3") (pintype "passive"))
      (node (ref "R18") (pin "1") (pinfunction "1_1") (pintype "passive"))
    )
    (net (code "76") (name "Net-(J5-3)") (class "Default")
      (node (ref "J5") (pin "P$3") (pinfunction "3_P$3") (pintype "passive"))
      (node (ref "R12") (pin "1") (pinfunction "1_1") (pintype "passive"))
    )
    (net (code "77") (name "Net-(J6-3)") (class "Default")
      (node (ref "J6") (pin "P$3") (pinfunction "3_P$3") (pintype "passive"))
      (node (ref "R17") (pin "1") (pinfunction "1_1") (pintype "passive"))
    )
    (net (code "78") (name "Net-(JP1-Pad5)") (class "Default")
      (node (ref "JP1") (pin "5") (pinfunction "5_5") (pintype "passive"))
      (node (ref "R3") (pin "2") (pinfunction "2_2") (pintype "passive"))
    )
    (net (code "79") (name "Net-(LED1-CBLUE)") (class "Default")
      (node (ref "LED1") (pin "P4") (pinfunction "CBLUE_P4") (pintype "passive"))
      (node (ref "R10") (pin "2") (pinfunction "2_2") (pintype "passive"))
    )
    (net (code "80") (name "Net-(LED1-CGREEN)") (class "Default")
      (node (ref "LED1") (pin "P2") (pinfunction "CGREEN_P2") (pintype "passive"))
      (node (ref "R11") (pin "2") (pinfunction "2_2") (pintype "passive"))
    )
    (net (code "81") (name "Net-(LED1-CRED)") (class "Default")
      (node (ref "LED1") (pin "P1") (pinfunction "CRED_P1") (pintype "passive"))
      (node (ref "R9") (pin "2") (pinfunction "2_2") (pintype "passive"))
    )
    (net (code "82") (name "Net-(P1-Pad3)") (class "Default")
      (node (ref "P1") (pin "3") (pinfunction "3_3") (pintype "bidirectional"))
      (node (ref "R42") (pin "2") (pinfunction "2_2") (pintype "passive"))
    )
    (net (code "83") (name "Net-(P2-Pad3)") (class "Default")
      (node (ref "P2") (pin "3") (pinfunction "3_3") (pintype "bidirectional"))
      (node (ref "R41") (pin "2") (pinfunction "2_2") (pintype "passive"))
    )
    (net (code "84") (name "Net-(T1-B)") (class "Default")
      (node (ref "R1") (pin "2") (pinfunction "2_2") (pintype "passive"))
      (node (ref "R2") (pin "2") (pinfunction "2_2") (pintype "passive"))
      (node (ref "T1") (pin "1") (pinfunction "B_1") (pintype "passive"))
    )
    (net (code "85") (name "unconnected-(J2-4-PadP$2)") (class "Default")
      (node (ref "J2") (pin "P$2") (pinfunction "4_P$2") (pintype "passive"))
    )
    (net (code "86") (name "unconnected-(J7-PadGNDBREAK)") (class "Default")
      (node (ref "J7") (pin "GNDBREAK") (pinfunction "GNDBREAK_GNDBREAK") (pintype "bidirectional"))
    )
    (net (code "87") (name "unconnected-(X2-Pad4)") (class "Default")
      (node (ref "X2") (pin "4") (pinfunction "4_4") (pintype "passive"))
    )
    (net (code "88") (name "unconnected-(X2-Pad5)") (class "Default")
      (node (ref "X2") (pin "5") (pinfunction "5_5") (pintype "passive"))
    )
  )
)
